# Wheel_Module.net
KiCad netlist of a schematic drawn in Altium Designer
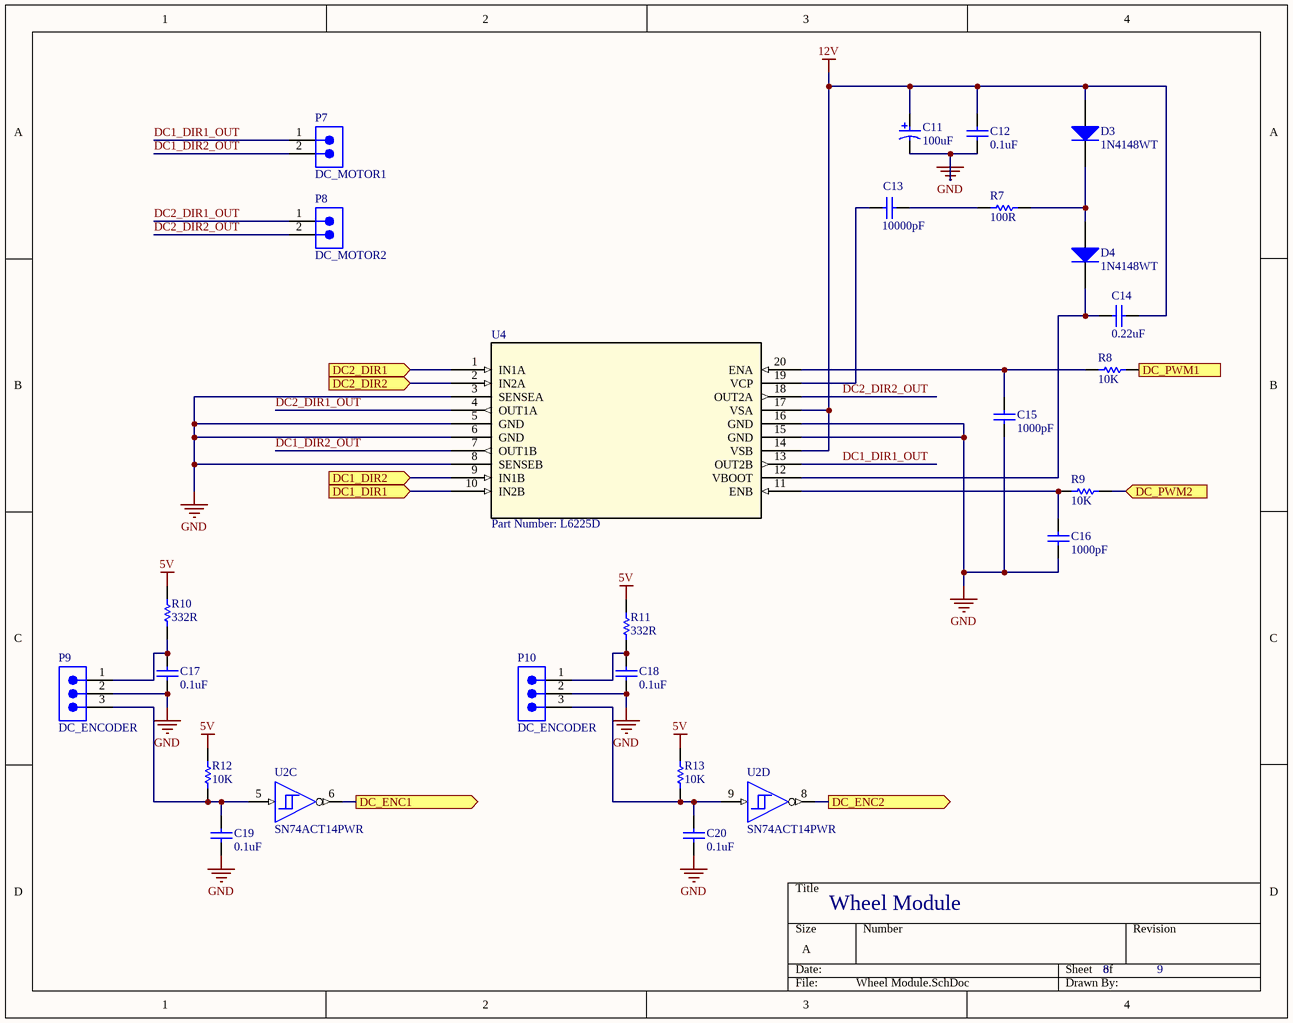
[diagram p0: Wheel Module.SchDoc]

(export (version "E")
  (design (tool "Eeschema 10.0.6"))
  (components
    (comp (ref "C11")
      (value "100uF")
      (footprint "NIC-CAPA2-6.3X5.8_V")
      (fields (field (name "PARTNUMBER") "UUD1C101MCL1GS") (field (name "MANUFACTURER") "Nichicon"))
      (libsource (lib "Altium Content Vault") (part "NIC-CAP-P-2"))
    )
    (comp (ref "C12")
      (value "0.1uF")
      (footprint "CAPC1608X90X35LL15T15")
      (description "Chip Capacitor, 100 nF, +/- 10%, 50 V, -55 to 125 degC, 0603 (1608 Metric), RoHS, Tape and Reel")
      (fields (field (name "TOLERANCE") "10%"))
      (libsource (lib "Altium Content Vault") (part "CAP-NP-2"))
    )
    (comp (ref "C13")
      (value "10000pF")
      (footprint "CAPC1608X90X35LL15T15")
      (fields
        (field (name "MANUFACTURER") "AVX Interconnect / Elco")
        (field (name "PART NUMBER") "06035C-103KAT2A")
      )
      (libsource (lib "Altium Content Vault") (part "CAP"))
    )
    (comp (ref "C14")
      (value "0.22uF")
      (footprint "CAPC1608X90X35ML10T15")
      (fields (field (name "MANUFACTURER") "Murata") (field (name "PART NUMBER") "GRM188F51H224ZA01D"))
      (libsource (lib "Altium Content Vault") (part "CAP"))
    )
    (comp (ref "C15")
      (value "1000pF")
      (footprint "CAPC2013X140X50NL20T25")
      (fields
        (field (name "MANUFACTURER") "AVX Interconnect / Elco")
        (field (name "PART NUMBER") "08051A102JAT2A")
      )
      (libsource (lib "Altium Content Vault") (part "CAP"))
    )
    (comp (ref "C16")
      (value "1000pF")
      (footprint "CAPC2013X140X50NL20T25")
      (fields
        (field (name "MANUFACTURER") "AVX Interconnect / Elco")
        (field (name "PART NUMBER") "08051A102JAT2A")
      )
      (libsource (lib "Altium Content Vault") (part "CAP"))
    )
    (comp (ref "C17")
      (value "0.1uF")
      (footprint "CAPC1608X90X35LL15T15")
      (description "Chip Capacitor, 100 nF, +/- 10%, 50 V, -55 to 125 degC, 0603 (1608 Metric), RoHS, Tape and Reel")
      (fields (field (name "TOLERANCE") "10%"))
      (libsource (lib "Altium Content Vault") (part "CAP-NP-2"))
    )
    (comp (ref "C18")
      (value "0.1uF")
      (footprint "CAPC1608X90X35LL15T15")
      (description "Chip Capacitor, 100 nF, +/- 10%, 50 V, -55 to 125 degC, 0603 (1608 Metric), RoHS, Tape and Reel")
      (fields (field (name "TOLERANCE") "10%"))
      (libsource (lib "Altium Content Vault") (part "CAP-NP-2"))
    )
    (comp (ref "C19")
      (value "0.1uF")
      (footprint "CAPC1608X90X35LL15T15")
      (description "Chip Capacitor, 100 nF, +/- 10%, 50 V, -55 to 125 degC, 0603 (1608 Metric), RoHS, Tape and Reel")
      (fields (field (name "TOLERANCE") "10%"))
      (libsource (lib "Altium Content Vault") (part "CAP-NP-2"))
    )
    (comp (ref "C20")
      (value "0.1uF")
      (footprint "CAPC1608X90X35LL15T15")
      (description "Chip Capacitor, 100 nF, +/- 10%, 50 V, -55 to 125 degC, 0603 (1608 Metric), RoHS, Tape and Reel")
      (fields (field (name "TOLERANCE") "10%"))
      (libsource (lib "Altium Content Vault") (part "CAP-NP-2"))
    )
    (comp (ref "D3")
      (value "1N4148WT")
      (footprint "FAIR-SOD-523F-2_V")
      (description "High Conductance Fast Switching Diode, 75 V, -55 to 150 degC, 2-Pin SOD523F, RoHS")
      (fields (field (name "MANUFACTURER") "Fairchild Semiconductor"))
      (libsource (lib "Altium Content Vault") (part "FAIR-D_K1A2-2"))
    )
    (comp (ref "D4")
      (value "1N4148WT")
      (footprint "FAIR-SOD-523F-2_V")
      (description "High Conductance Fast Switching Diode, 75 V, -55 to 150 degC, 2-Pin SOD523F, RoHS")
      (fields (field (name "MANUFACTURER") "Fairchild Semiconductor"))
      (libsource (lib "Altium Content Vault") (part "FAIR-D_K1A2-2"))
    )
    (comp (ref "P7")
      (value "DC_MOTOR1")
      (footprint "SMTC-DW-02-16-X-S-200")
      (fields (field (name "PARTNUMBER") "DW-02-16-G-S-200") (field (name "MANUFACTURER") "Samtec"))
      (libsource (lib "Altium Content Vault") (part "SMTC-DW-02-16-X-S-200"))
    )
    (comp (ref "P8")
      (value "DC_MOTOR2")
      (footprint "SMTC-DW-02-16-X-S-200")
      (fields (field (name "PARTNUMBER") "DW-02-16-G-S-200") (field (name "MANUFACTURER") "Samtec"))
      (libsource (lib "Altium Content Vault") (part "SMTC-DW-02-16-X-S-200"))
    )
    (comp (ref "P9")
      (value "DC_ENCODER")
      (footprint "SMTC-TSW-103-07-X-S")
      (description "0.025\" SQ Post Header, Through-hole, Vertical, -55 to 125 degC, 2.54 mm Pitch, 3-Pin, Male, RoHS")
      (fields (field (name "MANUFACTURER") "Samtec") (field (name "PARTNUMBER") "TSW-103-07-L-S"))
      (libsource (lib "Altium Content Vault") (part "SMTC-TSW-103-X-X-S-X"))
    )
    (comp (ref "P10")
      (value "DC_ENCODER")
      (footprint "SMTC-TSW-103-07-X-S")
      (description "0.025\" SQ Post Header, Through-hole, Vertical, -55 to 125 degC, 2.54 mm Pitch, 3-Pin, Male, RoHS")
      (fields (field (name "MANUFACTURER") "Samtec") (field (name "PARTNUMBER") "TSW-103-07-L-S"))
      (libsource (lib "Altium Content Vault") (part "SMTC-TSW-103-X-X-S-X"))
    )
    (comp (ref "R7")
      (value "100R")
      (footprint "RESC1609X50X30ML10T20")
      (fields (field (name "PART NUMBER") "CRCW0603100RJNEA") (field (name "MANUFACTURER") "Vishay Dale"))
      (libsource (lib "Altium Content Vault") (part "RES"))
    )
    (comp (ref "R8")
      (value "10K")
      (footprint "RESC1609X50X30ML10T20")
      (fields (field (name "MANUFACTURER") "Vishay Dale") (field (name "PART NUMBER") "CRCW060310K0JNEA"))
      (libsource (lib "Altium Content Vault") (part "RES"))
    )
    (comp (ref "R9")
      (value "10K")
      (footprint "RESC1609X50X30ML10T20")
      (fields (field (name "MANUFACTURER") "Vishay Dale") (field (name "PART NUMBER") "CRCW060310K0JNEA"))
      (libsource (lib "Altium Content Vault") (part "RES"))
    )
    (comp (ref "R10")
      (value "332R")
      (footprint "RESC1608X55X30ML15T15")
      (fields (field (name "PART NUMBER") "ERJ-3EKF3320V") (field (name "MANUFACTURER") "Panasonic"))
      (libsource (lib "Altium Content Vault") (part "RES"))
    )
    (comp (ref "R11")
      (value "332R")
      (footprint "RESC1608X55X30ML15T15")
      (fields (field (name "PART NUMBER") "ERJ-3EKF3320V") (field (name "MANUFACTURER") "Panasonic"))
      (libsource (lib "Altium Content Vault") (part "RES"))
    )
    (comp (ref "R12")
      (value "10K")
      (footprint "RESC1609X50X30ML10T20")
      (fields (field (name "MANUFACTURER") "Vishay Dale") (field (name "PART NUMBER") "CRCW060310K0JNEA"))
      (libsource (lib "Altium Content Vault") (part "RES"))
    )
    (comp (ref "R13")
      (value "10K")
      (footprint "RESC1609X50X30ML10T20")
      (fields (field (name "MANUFACTURER") "Vishay Dale") (field (name "PART NUMBER") "CRCW060310K0JNEA"))
      (libsource (lib "Altium Content Vault") (part "RES"))
    )
    (comp (ref "U2")
      (value "SN74ACT14PWR")
      (footprint "PW0014A_N")
      (description "Hex Schmitt-Trigger Inverters, PW0014A, LARGE T&R")
      (fields
        (field (name "GENERIC PART NUMBER") "SN74ACT14")
        (field (name "MANUFACTURER") "Texas Instruments")
      )
      (libsource (lib "Altium Content Vault") (part "TI-CD_SNX4XXXXXX4X_19A-14-SCHMITT"))
    )
    (comp (ref "U4")
      (value "Part Number: L6225D")
      (footprint "SO-20")
      (description "No Description Available")
      (fields
        (field (name "MANUFACTURER_PART_NUMBER") "L6225D")
        (field (name "COPYRIGHT") "Copyright (C) 2018 Accelerated Designs. All rights reserved")
      )
      (libsource (lib "L6225D") (part "L6225D"))
    )
  )
  (nets
    (net (code "1") (name "/DC1_DIR1") (class "Default")
      (node (ref "U4") (pin "10") (pinfunction "IN2B_10") (pintype "input"))
    )
    (net (code "2") (name "/DC1_DIR1_OUT") (class "Default")
      (node (ref "P7") (pin "1") (pinfunction "1_1") (pintype "passive"))
      (node (ref "U4") (pin "13") (pinfunction "OUT2B_13") (pintype "output"))
    )
    (net (code "3") (name "/DC1_DIR2") (class "Default")
      (node (ref "U4") (pin "9") (pinfunction "IN1B_9") (pintype "input"))
    )
    (net (code "4") (name "/DC1_DIR2_OUT") (class "Default")
      (node (ref "P7") (pin "2") (pinfunction "2_2") (pintype "passive"))
      (node (ref "U4") (pin "7") (pinfunction "OUT1B_7") (pintype "output"))
    )
    (net (code "5") (name "/DC2_DIR1") (class "Default")
      (node (ref "U4") (pin "1") (pinfunction "IN1A_1") (pintype "input"))
    )
    (net (code "6") (name "/DC2_DIR1_OUT") (class "Default")
      (node (ref "P8") (pin "1") (pinfunction "1_1") (pintype "passive"))
      (node (ref "U4") (pin "4") (pinfunction "OUT1A_4") (pintype "output"))
    )
    (net (code "7") (name "/DC2_DIR2") (class "Default")
      (node (ref "U4") (pin "2") (pinfunction "IN2A_2") (pintype "input"))
    )
    (net (code "8") (name "/DC2_DIR2_OUT") (class "Default")
      (node (ref "P8") (pin "2") (pinfunction "2_2") (pintype "passive"))
      (node (ref "U4") (pin "18") (pinfunction "OUT2A_18") (pintype "output"))
    )
    (net (code "9") (name "/DC_ENC1") (class "Default")
      (node (ref "U2") (pin "6") (pinfunction "~{3Y}_6") (pintype "output"))
    )
    (net (code "10") (name "/DC_ENC2") (class "Default")
      (node (ref "U2") (pin "8") (pinfunction "~{4Y}_8") (pintype "output"))
    )
    (net (code "11") (name "/DC_PWM1") (class "Default")
      (node (ref "R8") (pin "1") (pinfunction "1_1") (pintype "passive"))
    )
    (net (code "12") (name "/DC_PWM2") (class "Default")
      (node (ref "R9") (pin "1") (pinfunction "1_1") (pintype "passive"))
    )
    (net (code "13") (name "5V") (class "Default")
      (node (ref "R10") (pin "2") (pinfunction "2_2") (pintype "passive"))
      (node (ref "R11") (pin "2") (pinfunction "2_2") (pintype "passive"))
      (node (ref "R12") (pin "1") (pinfunction "1_1") (pintype "passive"))
      (node (ref "R13") (pin "1") (pinfunction "1_1") (pintype "passive"))
    )
    (net (code "14") (name "12V") (class "Default")
      (node (ref "C11") (pin "1") (pinfunction "1_1") (pintype "passive"))
      (node (ref "C12") (pin "2") (pinfunction "2_2") (pintype "passive"))
      (node (ref "C14") (pin "2") (pinfunction "2_2") (pintype "passive"))
      (node (ref "D3") (pin "2") (pinfunction "A_2") (pintype "passive"))
      (node (ref "U4") (pin "14") (pinfunction "VSB_14") (pintype "power_in"))
      (node (ref "U4") (pin "17") (pinfunction "VSA_17") (pintype "power_in"))
    )
    (net (code "15") (name "GND") (class "Default")
      (node (ref "C11") (pin "2") (pinfunction "2_2") (pintype "passive"))
      (node (ref "C12") (pin "1") (pinfunction "1_1") (pintype "passive"))
      (node (ref "C15") (pin "1") (pinfunction "1_1") (pintype "passive"))
      (node (ref "C16") (pin "1") (pinfunction "1_1") (pintype "passive"))
      (node (ref "C17") (pin "1") (pinfunction "1_1") (pintype "passive"))
      (node (ref "C18") (pin "1") (pinfunction "1_1") (pintype "passive"))
      (node (ref "C19") (pin "1") (pinfunction "1_1") (pintype "passive"))
      (node (ref "C20") (pin "1") (pinfunction "1_1") (pintype "passive"))
      (node (ref "P10") (pin "2") (pinfunction "Ground_2") (pintype "passive"))
      (node (ref "P9") (pin "2") (pinfunction "Ground_2") (pintype "passive"))
      (node (ref "U4") (pin "15") (pinfunction "GND_15") (pintype "passive"))
      (node (ref "U4") (pin "16") (pinfunction "GND_16") (pintype "passive"))
      (node (ref "U4") (pin "3") (pinfunction "SENSEA_3") (pintype "power_in"))
      (node (ref "U4") (pin "5") (pinfunction "GND_5") (pintype "passive"))
      (node (ref "U4") (pin "6") (pinfunction "GND_6") (pintype "passive"))
      (node (ref "U4") (pin "8") (pinfunction "SENSEB_8") (pintype "power_in"))
    )
    (net (code "16") (name "Net-(C13-Pad2)") (class "Default")
      (node (ref "C13") (pin "2") (pinfunction "2_2") (pintype "passive"))
      (node (ref "R7") (pin "1") (pinfunction "1_1") (pintype "passive"))
    )
    (net (code "17") (name "Net-(D3-K)") (class "Default")
      (node (ref "D3") (pin "1") (pinfunction "K_1") (pintype "passive"))
      (node (ref "D4") (pin "2") (pinfunction "A_2") (pintype "passive"))
      (node (ref "R7") (pin "2") (pinfunction "2_2") (pintype "passive"))
    )
    (net (code "18") (name "Net-(D4-K)") (class "Default")
      (node (ref "C14") (pin "1") (pinfunction "1_1") (pintype "passive"))
      (node (ref "D4") (pin "1") (pinfunction "K_1") (pintype "passive"))
      (node (ref "U4") (pin "12") (pinfunction "VBOOT_12") (pintype "power_in"))
    )
    (net (code "19") (name "Net-(P9-5V)") (class "Default")
      (node (ref "C17") (pin "2") (pinfunction "2_2") (pintype "passive"))
      (node (ref "P9") (pin "1") (pinfunction "5V_1") (pintype "passive"))
      (node (ref "R10") (pin "1") (pinfunction "1_1") (pintype "passive"))
    )
    (net (code "20") (name "Net-(P9-Signal)") (class "Default")
      (node (ref "C19") (pin "2") (pinfunction "2_2") (pintype "passive"))
      (node (ref "P9") (pin "3") (pinfunction "Signal_3") (pintype "passive"))
      (node (ref "R12") (pin "2") (pinfunction "2_2") (pintype "passive"))
      (node (ref "U2") (pin "5") (pinfunction "3A_5") (pintype "input"))
    )
    (net (code "21") (name "Net-(P10-5V)") (class "Default")
      (node (ref "C18") (pin "2") (pinfunction "2_2") (pintype "passive"))
      (node (ref "P10") (pin "1") (pinfunction "5V_1") (pintype "passive"))
      (node (ref "R11") (pin "1") (pinfunction "1_1") (pintype "passive"))
    )
    (net (code "22") (name "Net-(P10-Signal)") (class "Default")
      (node (ref "C20") (pin "2") (pinfunction "2_2") (pintype "passive"))
      (node (ref "P10") (pin "3") (pinfunction "Signal_3") (pintype "passive"))
      (node (ref "R13") (pin "2") (pinfunction "2_2") (pintype "passive"))
      (node (ref "U2") (pin "9") (pinfunction "4A_9") (pintype "input"))
    )
    (net (code "23") (name "Net-(U4-ENA)") (class "Default")
      (node (ref "C15") (pin "2") (pinfunction "2_2") (pintype "passive"))
      (node (ref "R8") (pin "2") (pinfunction "2_2") (pintype "passive"))
      (node (ref "U4") (pin "20") (pinfunction "ENA_20") (pintype "input"))
    )
    (net (code "24") (name "Net-(U4-ENB)") (class "Default")
      (node (ref "C16") (pin "2") (pinfunction "2_2") (pintype "passive"))
      (node (ref "R9") (pin "2") (pinfunction "2_2") (pintype "passive"))
      (node (ref "U4") (pin "11") (pinfunction "ENB_11") (pintype "input"))
    )
    (net (code "25") (name "Net-(U4-VCP)") (class "Default")
      (node (ref "C13") (pin "1") (pinfunction "1_1") (pintype "passive"))
      (node (ref "U4") (pin "19") (pinfunction "VCP_19") (pintype "power_in"))
    )
  )
)
